# laser_driver.net
KiCad netlist of a schematic drawn in Altium Designer
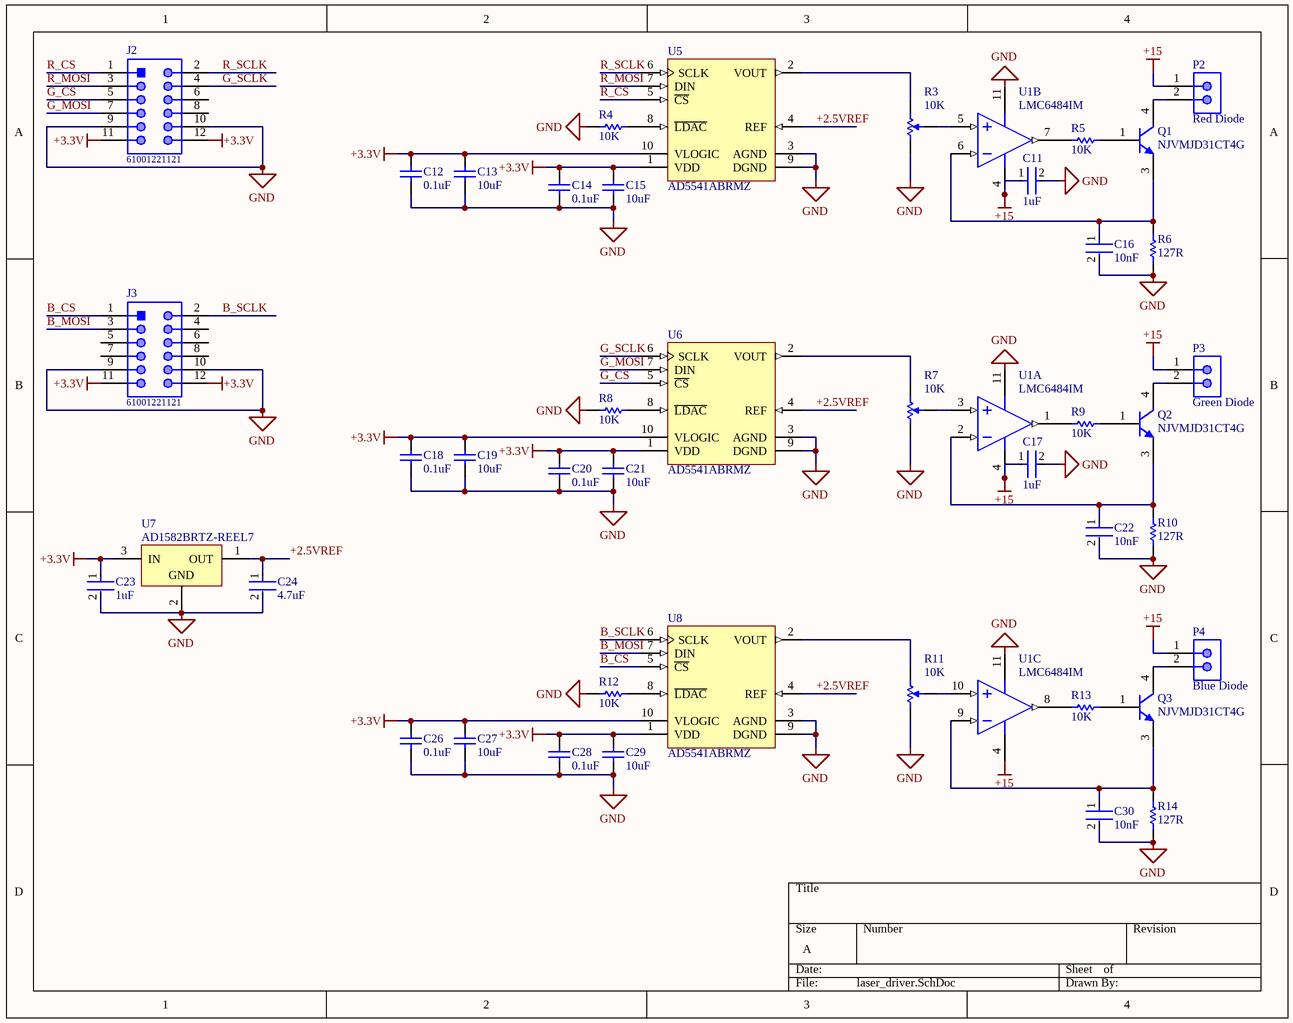
[diagram p0: laser_driver.SchDoc]

(export (version "E")
  (design (tool "Eeschema 10.0.6"))
  (components
    (comp (ref "C11")
      (value "1uF")
      (footprint "FP-CC0603-DA-MFG")
      (description "CAP CER 1UF 16V X7R 0603")
      (fields (field (name "TOLERANCE") "0.1") (field (name "MANUFACTURER") "YAGEO"))
      (libsource (lib "Altium Content Vault") (part "11868f565c42a9108669ba33697ecf6"))
    )
    (comp (ref "C12")
      (value "0.1uF")
      (footprint "CAPC1608X87X35NL15T15")
      (description "C0603X104K5RACTU")
      (fields (field (name "MANUFACTURER") "Kemet"))
      (libsource (lib "Altium Content Vault") (part "CAP"))
    )
    (comp (ref "C13")
      (value "10uF")
      (footprint "CAPC1608X90X35NL10T15")
      (description "GRM188R60J106ME47D")
      (fields (field (name "MANUFACTURER") "Murata"))
      (libsource (lib "Altium Content Vault") (part "CAP"))
    )
    (comp (ref "C14")
      (value "0.1uF")
      (footprint "CAPC1608X87X35NL15T15")
      (description "C0603X104K5RACTU")
      (fields (field (name "MANUFACTURER") "Kemet"))
      (libsource (lib "Altium Content Vault") (part "CAP"))
    )
    (comp (ref "C15")
      (value "10uF")
      (footprint "CAPC1608X90X35NL10T15")
      (description "GRM188R60J106ME47D")
      (fields (field (name "MANUFACTURER") "Murata"))
      (libsource (lib "Altium Content Vault") (part "CAP"))
    )
    (comp (ref "C16")
      (value "10nF")
      (footprint "FP-CGA3E-0_3-0_1-IPC_A")
      (description "Cap Ceramic 10nF 100V X8R 10% Pad SMD 0603 +150°C Automotive T/R")
      (fields (field (name "TOLERANCE") "10%"))
      (libsource (lib "Altium Content Vault") (part "b4654b650e69147ec39a6b967a45e02"))
    )
    (comp (ref "C17")
      (value "1uF")
      (footprint "FP-CC0603-DA-MFG")
      (description "CAP CER 1UF 16V X7R 0603")
      (fields (field (name "TOLERANCE") "0.1") (field (name "MANUFACTURER") "YAGEO"))
      (libsource (lib "Altium Content Vault") (part "11868f565c42a9108669ba33697ecf6"))
    )
    (comp (ref "C18")
      (value "0.1uF")
      (footprint "CAPC1608X87X35NL15T15")
      (description "C0603X104K5RACTU")
      (fields (field (name "MANUFACTURER") "Kemet"))
      (libsource (lib "Altium Content Vault") (part "CAP"))
    )
    (comp (ref "C19")
      (value "10uF")
      (footprint "CAPC1608X90X35NL10T15")
      (description "GRM188R60J106ME47D")
      (fields (field (name "MANUFACTURER") "Murata"))
      (libsource (lib "Altium Content Vault") (part "CAP"))
    )
    (comp (ref "C20")
      (value "0.1uF")
      (footprint "CAPC1608X87X35NL15T15")
      (description "C0603X104K5RACTU")
      (fields (field (name "MANUFACTURER") "Kemet"))
      (libsource (lib "Altium Content Vault") (part "CAP"))
    )
    (comp (ref "C21")
      (value "10uF")
      (footprint "CAPC1608X90X35NL10T15")
      (description "GRM188R60J106ME47D")
      (fields (field (name "MANUFACTURER") "Murata"))
      (libsource (lib "Altium Content Vault") (part "CAP"))
    )
    (comp (ref "C22")
      (value "10nF")
      (footprint "FP-CGA3E-0_3-0_1-IPC_A")
      (description "Cap Ceramic 10nF 100V X8R 10% Pad SMD 0603 +150°C Automotive T/R")
      (fields (field (name "TOLERANCE") "10%"))
      (libsource (lib "Altium Content Vault") (part "b4654b650e69147ec39a6b967a45e02"))
    )
    (comp (ref "C23")
      (value "1uF")
      (footprint "FP-CC0603-DA-MFG")
      (description "CAP CER 1UF 16V X7R 0603")
      (fields (field (name "TOLERANCE") "0.1") (field (name "MANUFACTURER") "YAGEO"))
      (libsource (lib "Altium Content Vault") (part "11868f565c42a9108669ba33697ecf6"))
    )
    (comp (ref "C24")
      (value "4.7uF")
      (footprint "FP-C0603-CG-MFG")
      (description "CAP CER 4.7UF 6.3V X5R 0603")
      (fields (field (name "TOLERANCE") "10%") (field (name "MANUFACTURER") "Kemet"))
      (libsource (lib "Altium Content Vault") (part "11868f565c42a9108669ba33697ecf6"))
    )
    (comp (ref "C26")
      (value "0.1uF")
      (footprint "CAPC1608X87X35NL15T15")
      (description "C0603X104K5RACTU")
      (fields (field (name "MANUFACTURER") "Kemet"))
      (libsource (lib "Altium Content Vault") (part "CAP"))
    )
    (comp (ref "C27")
      (value "10uF")
      (footprint "CAPC1608X90X35NL10T15")
      (description "GRM188R60J106ME47D")
      (fields (field (name "MANUFACTURER") "Murata"))
      (libsource (lib "Altium Content Vault") (part "CAP"))
    )
    (comp (ref "C28")
      (value "0.1uF")
      (footprint "CAPC1608X87X35NL15T15")
      (description "C0603X104K5RACTU")
      (fields (field (name "MANUFACTURER") "Kemet"))
      (libsource (lib "Altium Content Vault") (part "CAP"))
    )
    (comp (ref "C29")
      (value "10uF")
      (footprint "CAPC1608X90X35NL10T15")
      (description "GRM188R60J106ME47D")
      (fields (field (name "MANUFACTURER") "Murata"))
      (libsource (lib "Altium Content Vault") (part "CAP"))
    )
    (comp (ref "C30")
      (value "10nF")
      (footprint "FP-CGA3E-0_3-0_1-IPC_A")
      (description "Cap Ceramic 10nF 100V X8R 10% Pad SMD 0603 +150°C Automotive T/R")
      (fields (field (name "TOLERANCE") "10%"))
      (libsource (lib "Altium Content Vault") (part "b4654b650e69147ec39a6b967a45e02"))
    )
    (comp (ref "J2")
      (value "61001221121")
      (footprint "61001221121")
      (description "SMT Vertical Pin Header WR-PHD, Pitch 2.54 mm, Dual Row, 12 pins")
      (fields (field (name "MANUFACTURER") "Wurth Elektronik") (field (name "PUBLISHER") "WurthElektronik"))
      (libsource (lib "Altium Content Vault") (part "WE-CN-2P-M-R12"))
    )
    (comp (ref "J3")
      (value "61001221121")
      (footprint "61001221121")
      (description "SMT Vertical Pin Header WR-PHD, Pitch 2.54 mm, Dual Row, 12 pins")
      (fields (field (name "MANUFACTURER") "Wurth Elektronik") (field (name "PUBLISHER") "WurthElektronik"))
      (libsource (lib "Altium Content Vault") (part "WE-CN-2P-M-R12"))
    )
    (comp (ref "P2")
      (value "Red Diode")
      (footprint "JST-B2B-XH-A_V")
      (fields (field (name "MANUFACTURER") "JST"))
      (libsource (lib "Altium Content Vault") (part "CN-1P-M-R2"))
    )
    (comp (ref "P3")
      (value "Green Diode")
      (footprint "JST-B2B-XH-A_V")
      (fields (field (name "MANUFACTURER") "JST"))
      (libsource (lib "Altium Content Vault") (part "CN-1P-M-R2"))
    )
    (comp (ref "P4")
      (value "Blue Diode")
      (footprint "JST-B2B-XH-A_V")
      (fields (field (name "MANUFACTURER") "JST"))
      (libsource (lib "Altium Content Vault") (part "CN-1P-M-R2"))
    )
    (comp (ref "Q1")
      (value "NJVMJD31CT4G")
      (footprint "ONSC-DPAK-3-369C-01_V")
      (description "Complementary Power Transistor, 3-Pin DPAK, Pb-Free, Tape and Reel")
      (fields (field (name "MANUFACTURER") "On Semiconductor"))
      (libsource (lib "Altium Content Vault") (part "ONSC-NPN-B1E3C4-3"))
    )
    (comp (ref "Q2")
      (value "NJVMJD31CT4G")
      (footprint "ONSC-DPAK-3-369C-01_V")
      (description "Complementary Power Transistor, 3-Pin DPAK, Pb-Free, Tape and Reel")
      (fields (field (name "MANUFACTURER") "On Semiconductor"))
      (libsource (lib "Altium Content Vault") (part "ONSC-NPN-B1E3C4-3"))
    )
    (comp (ref "Q3")
      (value "NJVMJD31CT4G")
      (footprint "ONSC-DPAK-3-369C-01_V")
      (description "Complementary Power Transistor, 3-Pin DPAK, Pb-Free, Tape and Reel")
      (fields (field (name "MANUFACTURER") "On Semiconductor"))
      (libsource (lib "Altium Content Vault") (part "ONSC-NPN-B1E3C4-3"))
    )
    (comp (ref "R3")
      (value "10K")
      (footprint "BOUR-3313J-1_V")
      (description "Trimming Potentiometer, 10 KOhm, -55 to 125 degC, 3-Pin SMD, RoHS, Tape and Reel")
      (fields (field (name "MANUFACTURER") "Bourns"))
      (libsource (lib "Altium Content Vault") (part "RES-ADJ-3_A"))
    )
    (comp (ref "R4")
      (value "10K")
      (footprint "RESC1609X55X30LL15T15")
      (description "Chip Resistor, 10 KOhm, +/- 1%, 0.1 W, -55 to 155 degC, 0603 (1608 Metric), RoHS, Tape and Reel")
      (fields (field (name "TOLERANCE") "1%") (field (name "MANUFACTURER") "Panasonic"))
      (libsource (lib "Altium Content Vault") (part "RES-2"))
    )
    (comp (ref "R5")
      (value "10K")
      (footprint "RESC1609X55X30LL15T15")
      (description "Chip Resistor, 10 KOhm, +/- 1%, 0.1 W, -55 to 155 degC, 0603 (1608 Metric), RoHS, Tape and Reel")
      (fields (field (name "TOLERANCE") "1%") (field (name "MANUFACTURER") "Panasonic"))
      (libsource (lib "Altium Content Vault") (part "RES-2"))
    )
    (comp (ref "R6")
      (value "127R")
      (footprint "RESC1608X55X30LL15T15")
      (description "ERJ-3EKF1270V")
      (fields (field (name "MANUFACTURER") "Panasonic"))
      (libsource (lib "Altium Content Vault") (part "RES"))
    )
    (comp (ref "R7")
      (value "10K")
      (footprint "BOUR-3313J-1_V")
      (description "Trimming Potentiometer, 10 KOhm, -55 to 125 degC, 3-Pin SMD, RoHS, Tape and Reel")
      (fields (field (name "MANUFACTURER") "Bourns"))
      (libsource (lib "Altium Content Vault") (part "RES-ADJ-3_A"))
    )
    (comp (ref "R8")
      (value "10K")
      (footprint "RESC1609X55X30LL15T15")
      (description "Chip Resistor, 10 KOhm, +/- 1%, 0.1 W, -55 to 155 degC, 0603 (1608 Metric), RoHS, Tape and Reel")
      (fields (field (name "TOLERANCE") "1%") (field (name "MANUFACTURER") "Panasonic"))
      (libsource (lib "Altium Content Vault") (part "RES-2"))
    )
    (comp (ref "R9")
      (value "10K")
      (footprint "RESC1609X55X30LL15T15")
      (description "Chip Resistor, 10 KOhm, +/- 1%, 0.1 W, -55 to 155 degC, 0603 (1608 Metric), RoHS, Tape and Reel")
      (fields (field (name "TOLERANCE") "1%") (field (name "MANUFACTURER") "Panasonic"))
      (libsource (lib "Altium Content Vault") (part "RES-2"))
    )
    (comp (ref "R10")
      (value "127R")
      (footprint "RESC1608X55X30LL15T15")
      (description "ERJ-3EKF1270V")
      (fields (field (name "MANUFACTURER") "Panasonic"))
      (libsource (lib "Altium Content Vault") (part "RES"))
    )
    (comp (ref "R11")
      (value "10K")
      (footprint "BOUR-3313J-1_V")
      (description "Trimming Potentiometer, 10 KOhm, -55 to 125 degC, 3-Pin SMD, RoHS, Tape and Reel")
      (fields (field (name "MANUFACTURER") "Bourns"))
      (libsource (lib "Altium Content Vault") (part "RES-ADJ-3_A"))
    )
    (comp (ref "R12")
      (value "10K")
      (footprint "RESC1609X55X30LL15T15")
      (description "Chip Resistor, 10 KOhm, +/- 1%, 0.1 W, -55 to 155 degC, 0603 (1608 Metric), RoHS, Tape and Reel")
      (fields (field (name "TOLERANCE") "1%") (field (name "MANUFACTURER") "Panasonic"))
      (libsource (lib "Altium Content Vault") (part "RES-2"))
    )
    (comp (ref "R13")
      (value "10K")
      (footprint "RESC1609X55X30LL15T15")
      (description "Chip Resistor, 10 KOhm, +/- 1%, 0.1 W, -55 to 155 degC, 0603 (1608 Metric), RoHS, Tape and Reel")
      (fields (field (name "TOLERANCE") "1%") (field (name "MANUFACTURER") "Panasonic"))
      (libsource (lib "Altium Content Vault") (part "RES-2"))
    )
    (comp (ref "R14")
      (value "127R")
      (footprint "RESC1608X55X30LL15T15")
      (description "ERJ-3EKF1270V")
      (fields (field (name "MANUFACTURER") "Panasonic"))
      (libsource (lib "Altium Content Vault") (part "RES"))
    )
    (comp (ref "U1")
      (value "LMC6484IM")
      (footprint "D0014A_N")
      (description "CMOS Quad Rail to Rail Input and Output Operational Amplifier, 14-pin Narrow SOIC, Pb-Free")
      (fields (field (name "MANUFACTURER") "Texas Instruments"))
      (libsource (lib "Altium Content Vault") (part "AMP-OPA-LF147-14"))
    )
    (comp (ref "U5")
      (value "AD5541ABRMZ")
      (footprint "RM-10_L")
      (fields (field (name "GENERIC PART NUMBER") "AD5541A") (field (name "MANUFACTURER") "Analog Devices"))
      (libsource (lib "Altium Content Vault") (part "ADI-AD5541A-RM-10"))
    )
    (comp (ref "U6")
      (value "AD5541ABRMZ")
      (footprint "RM-10_L")
      (fields (field (name "GENERIC PART NUMBER") "AD5541A") (field (name "MANUFACTURER") "Analog Devices"))
      (libsource (lib "Altium Content Vault") (part "ADI-AD5541A-RM-10"))
    )
    (comp (ref "U7")
      (value "AD1582BRTZ-REEL7")
      (footprint "ADI-RT-3_M")
      (fields (field (name "MANUFACTURER") "Analog Devices"))
      (libsource (lib "Altium Content Vault") (part "ADI-AD158X-RT-3"))
    )
    (comp (ref "U8")
      (value "AD5541ABRMZ")
      (footprint "RM-10_L")
      (fields (field (name "GENERIC PART NUMBER") "AD5541A") (field (name "MANUFACTURER") "Analog Devices"))
      (libsource (lib "Altium Content Vault") (part "ADI-AD5541A-RM-10"))
    )
  )
  (nets
    (net (code "1") (name "+3.3V") (class "Default")
      (node (ref "C12") (pin "1") (pinfunction "1_1") (pintype "passive"))
      (node (ref "C13") (pin "2") (pinfunction "2_2") (pintype "passive"))
      (node (ref "C14") (pin "1") (pinfunction "1_1") (pintype "passive"))
      (node (ref "C15") (pin "2") (pinfunction "2_2") (pintype "passive"))
      (node (ref "C18") (pin "1") (pinfunction "1_1") (pintype "passive"))
      (node (ref "C19") (pin "2") (pinfunction "2_2") (pintype "passive"))
      (node (ref "C20") (pin "1") (pinfunction "1_1") (pintype "passive"))
      (node (ref "C21") (pin "2") (pinfunction "2_2") (pintype "passive"))
      (node (ref "C23") (pin "1") (pinfunction "1_1") (pintype "passive"))
      (node (ref "C26") (pin "1") (pinfunction "1_1") (pintype "passive"))
      (node (ref "C27") (pin "2") (pinfunction "2_2") (pintype "passive"))
      (node (ref "C28") (pin "1") (pinfunction "1_1") (pintype "passive"))
      (node (ref "C29") (pin "2") (pinfunction "2_2") (pintype "passive"))
      (node (ref "J2") (pin "11") (pinfunction "11_11") (pintype "passive"))
      (node (ref "J2") (pin "12") (pinfunction "12_12") (pintype "passive"))
      (node (ref "J3") (pin "11") (pinfunction "11_11") (pintype "passive"))
      (node (ref "J3") (pin "12") (pinfunction "12_12") (pintype "passive"))
      (node (ref "U5") (pin "1") (pinfunction "VDD_1") (pintype "power_in"))
      (node (ref "U5") (pin "10") (pinfunction "VLOGIC_10") (pintype "power_in"))
      (node (ref "U6") (pin "1") (pinfunction "VDD_1") (pintype "power_in"))
      (node (ref "U6") (pin "10") (pinfunction "VLOGIC_10") (pintype "power_in"))
      (node (ref "U7") (pin "3") (pinfunction "IN_3") (pintype "power_in"))
      (node (ref "U8") (pin "1") (pinfunction "VDD_1") (pintype "power_in"))
      (node (ref "U8") (pin "10") (pinfunction "VLOGIC_10") (pintype "power_in"))
    )
    (net (code "2") (name "+15") (class "Default")
      (node (ref "C11") (pin "1") (pinfunction "1_1") (pintype "passive"))
      (node (ref "C17") (pin "1") (pinfunction "1_1") (pintype "passive"))
      (node (ref "P2") (pin "1") (pinfunction "1_1") (pintype "passive"))
      (node (ref "P3") (pin "1") (pinfunction "1_1") (pintype "passive"))
      (node (ref "P4") (pin "1") (pinfunction "1_1") (pintype "passive"))
      (node (ref "U1") (pin "4") (pinfunction "V+_4") (pintype "power_in"))
    )
    (net (code "3") (name "/+2.5VREF") (class "Default")
      (node (ref "C24") (pin "1") (pinfunction "1_1") (pintype "passive"))
      (node (ref "U5") (pin "4") (pinfunction "REF_4") (pintype "input"))
      (node (ref "U6") (pin "4") (pinfunction "REF_4") (pintype "input"))
      (node (ref "U7") (pin "1") (pinfunction "OUT_1") (pintype "power_in"))
      (node (ref "U8") (pin "4") (pinfunction "REF_4") (pintype "input"))
    )
    (net (code "4") (name "/B_CS") (class "Default")
      (node (ref "J3") (pin "1") (pinfunction "1_1") (pintype "passive"))
      (node (ref "U8") (pin "5") (pinfunction "~{CS}_5") (pintype "input"))
    )
    (net (code "5") (name "/B_MOSI") (class "Default")
      (node (ref "J3") (pin "3") (pinfunction "3_3") (pintype "passive"))
      (node (ref "U8") (pin "7") (pinfunction "DIN_7") (pintype "input"))
    )
    (net (code "6") (name "/B_SCLK") (class "Default")
      (node (ref "J3") (pin "2") (pinfunction "2_2") (pintype "passive"))
      (node (ref "U8") (pin "6") (pinfunction "SCLK_6") (pintype "input"))
    )
    (net (code "7") (name "/G_CS") (class "Default")
      (node (ref "J2") (pin "5") (pinfunction "5_5") (pintype "passive"))
      (node (ref "U6") (pin "5") (pinfunction "~{CS}_5") (pintype "input"))
    )
    (net (code "8") (name "/G_MOSI") (class "Default")
      (node (ref "J2") (pin "7") (pinfunction "7_7") (pintype "passive"))
      (node (ref "U6") (pin "7") (pinfunction "DIN_7") (pintype "input"))
    )
    (net (code "9") (name "/G_SCLK") (class "Default")
      (node (ref "J2") (pin "4") (pinfunction "4_4") (pintype "passive"))
      (node (ref "U6") (pin "6") (pinfunction "SCLK_6") (pintype "input"))
    )
    (net (code "10") (name "/R_CS") (class "Default")
      (node (ref "J2") (pin "1") (pinfunction "1_1") (pintype "passive"))
      (node (ref "U5") (pin "5") (pinfunction "~{CS}_5") (pintype "input"))
    )
    (net (code "11") (name "/R_MOSI") (class "Default")
      (node (ref "J2") (pin "3") (pinfunction "3_3") (pintype "passive"))
      (node (ref "U5") (pin "7") (pinfunction "DIN_7") (pintype "input"))
    )
    (net (code "12") (name "/R_SCLK") (class "Default")
      (node (ref "J2") (pin "2") (pinfunction "2_2") (pintype "passive"))
      (node (ref "U5") (pin "6") (pinfunction "SCLK_6") (pintype "input"))
    )
    (net (code "13") (name "GND") (class "Default")
      (node (ref "C11") (pin "2") (pinfunction "2_2") (pintype "passive"))
      (node (ref "C12") (pin "2") (pinfunction "2_2") (pintype "passive"))
      (node (ref "C13") (pin "1") (pinfunction "1_1") (pintype "passive"))
      (node (ref "C14") (pin "2") (pinfunction "2_2") (pintype "passive"))
      (node (ref "C15") (pin "1") (pinfunction "1_1") (pintype "passive"))
      (node (ref "C16") (pin "2") (pinfunction "2_2") (pintype "passive"))
      (node (ref "C17") (pin "2") (pinfunction "2_2") (pintype "passive"))
      (node (ref "C18") (pin "2") (pinfunction "2_2") (pintype "passive"))
      (node (ref "C19") (pin "1") (pinfunction "1_1") (pintype "passive"))
      (node (ref "C20") (pin "2") (pinfunction "2_2") (pintype "passive"))
      (node (ref "C21") (pin "1") (pinfunction "1_1") (pintype "passive"))
      (node (ref "C22") (pin "2") (pinfunction "2_2") (pintype "passive"))
      (node (ref "C23") (pin "2") (pinfunction "2_2") (pintype "passive"))
      (node (ref "C24") (pin "2") (pinfunction "2_2") (pintype "passive"))
      (node (ref "C26") (pin "2") (pinfunction "2_2") (pintype "passive"))
      (node (ref "C27") (pin "1") (pinfunction "1_1") (pintype "passive"))
      (node (ref "C28") (pin "2") (pinfunction "2_2") (pintype "passive"))
      (node (ref "C29") (pin "1") (pinfunction "1_1") (pintype "passive"))
      (node (ref "C30") (pin "2") (pinfunction "2_2") (pintype "passive"))
      (node (ref "J2") (pin "10") (pinfunction "10_10") (pintype "passive"))
      (node (ref "J2") (pin "9") (pinfunction "9_9") (pintype "passive"))
      (node (ref "J3") (pin "10") (pinfunction "10_10") (pintype "passive"))
      (node (ref "J3") (pin "9") (pinfunction "9_9") (pintype "passive"))
      (node (ref "R10") (pin "1") (pinfunction "1_1") (pintype "passive"))
      (node (ref "R11") (pin "1") (pinfunction "1_1") (pintype "passive"))
      (node (ref "R12") (pin "2") (pinfunction "2_2") (pintype "passive"))
      (node (ref "R14") (pin "1") (pinfunction "1_1") (pintype "passive"))
      (node (ref "R3") (pin "1") (pinfunction "1_1") (pintype "passive"))
      (node (ref "R4") (pin "2") (pinfunction "2_2") (pintype "passive"))
      (node (ref "R6") (pin "1") (pinfunction "1_1") (pintype "passive"))
      (node (ref "R7") (pin "1") (pinfunction "1_1") (pintype "passive"))
      (node (ref "R8") (pin "2") (pinfunction "2_2") (pintype "passive"))
      (node (ref "U1") (pin "11") (pinfunction "V-_11") (pintype "power_in"))
      (node (ref "U5") (pin "3") (pinfunction "AGND_3") (pintype "power_in"))
      (node (ref "U5") (pin "9") (pinfunction "DGND_9") (pintype "power_in"))
      (node (ref "U6") (pin "3") (pinfunction "AGND_3") (pintype "power_in"))
      (node (ref "U6") (pin "9") (pinfunction "DGND_9") (pintype "power_in"))
      (node (ref "U7") (pin "2") (pinfunction "GND_2") (pintype "power_in"))
      (node (ref "U8") (pin "3") (pinfunction "AGND_3") (pintype "power_in"))
      (node (ref "U8") (pin "9") (pinfunction "DGND_9") (pintype "power_in"))
    )
    (net (code "14") (name "Net-(Q1-B)") (class "Default")
      (node (ref "Q1") (pin "1") (pinfunction "B_1") (pintype "passive"))
      (node (ref "R5") (pin "2") (pinfunction "2_2") (pintype "passive"))
    )
    (net (code "15") (name "Net-(Q1-C)") (class "Default")
      (node (ref "P2") (pin "2") (pinfunction "2_2") (pintype "passive"))
      (node (ref "Q1") (pin "4") (pinfunction "C_4") (pintype "passive"))
    )
    (net (code "16") (name "Net-(Q1-E)") (class "Default")
      (node (ref "C16") (pin "1") (pinfunction "1_1") (pintype "passive"))
      (node (ref "Q1") (pin "3") (pinfunction "E_3") (pintype "passive"))
      (node (ref "R6") (pin "2") (pinfunction "2_2") (pintype "passive"))
      (node (ref "U1") (pin "6") (pinfunction "IN2-_6") (pintype "input"))
    )
    (net (code "17") (name "Net-(Q2-B)") (class "Default")
      (node (ref "Q2") (pin "1") (pinfunction "B_1") (pintype "passive"))
      (node (ref "R9") (pin "2") (pinfunction "2_2") (pintype "passive"))
    )
    (net (code "18") (name "Net-(Q2-C)") (class "Default")
      (node (ref "P3") (pin "2") (pinfunction "2_2") (pintype "passive"))
      (node (ref "Q2") (pin "4") (pinfunction "C_4") (pintype "passive"))
    )
    (net (code "19") (name "Net-(Q2-E)") (class "Default")
      (node (ref "C22") (pin "1") (pinfunction "1_1") (pintype "passive"))
      (node (ref "Q2") (pin "3") (pinfunction "E_3") (pintype "passive"))
      (node (ref "R10") (pin "2") (pinfunction "2_2") (pintype "passive"))
      (node (ref "U1") (pin "2") (pinfunction "IN1-_2") (pintype "input"))
    )
    (net (code "20") (name "Net-(Q3-B)") (class "Default")
      (node (ref "Q3") (pin "1") (pinfunction "B_1") (pintype "passive"))
      (node (ref "R13") (pin "2") (pinfunction "2_2") (pintype "passive"))
    )
    (net (code "21") (name "Net-(Q3-C)") (class "Default")
      (node (ref "P4") (pin "2") (pinfunction "2_2") (pintype "passive"))
      (node (ref "Q3") (pin "4") (pinfunction "C_4") (pintype "passive"))
    )
    (net (code "22") (name "Net-(Q3-E)") (class "Default")
      (node (ref "C30") (pin "1") (pinfunction "1_1") (pintype "passive"))
      (node (ref "Q3") (pin "3") (pinfunction "E_3") (pintype "passive"))
      (node (ref "R14") (pin "2") (pinfunction "2_2") (pintype "passive"))
      (node (ref "U1") (pin "9") (pinfunction "IN3-_9") (pintype "input"))
    )
    (net (code "23") (name "Net-(U1A-IN1+)") (class "Default")
      (node (ref "R7") (pin "2") (pinfunction "2_2") (pintype "passive"))
      (node (ref "U1") (pin "3") (pinfunction "IN1+_3") (pintype "input"))
    )
    (net (code "24") (name "Net-(U1A-OUT1)") (class "Default")
      (node (ref "R9") (pin "1") (pinfunction "1_1") (pintype "passive"))
      (node (ref "U1") (pin "1") (pinfunction "OUT1_1") (pintype "output"))
    )
    (net (code "25") (name "Net-(U1B-IN2+)") (class "Default")
      (node (ref "R3") (pin "2") (pinfunction "2_2") (pintype "passive"))
      (node (ref "U1") (pin "5") (pinfunction "IN2+_5") (pintype "input"))
    )
    (net (code "26") (name "Net-(U1B-OUT2)") (class "Default")
      (node (ref "R5") (pin "1") (pinfunction "1_1") (pintype "passive"))
      (node (ref "U1") (pin "7") (pinfunction "OUT2_7") (pintype "output"))
    )
    (net (code "27") (name "Net-(U1C-IN3+)") (class "Default")
      (node (ref "R11") (pin "2") (pinfunction "2_2") (pintype "passive"))
      (node (ref "U1") (pin "10") (pinfunction "IN3+_10") (pintype "input"))
    )
    (net (code "28") (name "Net-(U1C-OUT3)") (class "Default")
      (node (ref "R13") (pin "1") (pinfunction "1_1") (pintype "passive"))
      (node (ref "U1") (pin "8") (pinfunction "OUT3_8") (pintype "output"))
    )
    (net (code "29") (name "Net-(U5-VOUT)") (class "Default")
      (node (ref "R3") (pin "3") (pinfunction "3_3") (pintype "passive"))
      (node (ref "U5") (pin "2") (pinfunction "VOUT_2") (pintype "output"))
    )
    (net (code "30") (name "Net-(U5-~{LDAC})") (class "Default")
      (node (ref "R4") (pin "1") (pinfunction "1_1") (pintype "passive"))
      (node (ref "U5") (pin "8") (pinfunction "~{LDAC}_8") (pintype "input"))
    )
    (net (code "31") (name "Net-(U6-VOUT)") (class "Default")
      (node (ref "R7") (pin "3") (pinfunction "3_3") (pintype "passive"))
      (node (ref "U6") (pin "2") (pinfunction "VOUT_2") (pintype "output"))
    )
    (net (code "32") (name "Net-(U6-~{LDAC})") (class "Default")
      (node (ref "R8") (pin "1") (pinfunction "1_1") (pintype "passive"))
      (node (ref "U6") (pin "8") (pinfunction "~{LDAC}_8") (pintype "input"))
    )
    (net (code "33") (name "Net-(U8-VOUT)") (class "Default")
      (node (ref "R11") (pin "3") (pinfunction "3_3") (pintype "passive"))
      (node (ref "U8") (pin "2") (pinfunction "VOUT_2") (pintype "output"))
    )
    (net (code "34") (name "Net-(U8-~{LDAC})") (class "Default")
      (node (ref "R12") (pin "1") (pinfunction "1_1") (pintype "passive"))
      (node (ref "U8") (pin "8") (pinfunction "~{LDAC}_8") (pintype "input"))
    )
    (net (code "35") (name "unconnected-(J2-Pad6)") (class "Default")
      (node (ref "J2") (pin "6") (pinfunction "6_6") (pintype "passive"))
    )
    (net (code "36") (name "unconnected-(J2-Pad8)") (class "Default")
      (node (ref "J2") (pin "8") (pinfunction "8_8") (pintype "passive"))
    )
    (net (code "37") (name "unconnected-(J3-Pad4)") (class "Default")
      (node (ref "J3") (pin "4") (pinfunction "4_4") (pintype "passive"))
    )
    (net (code "38") (name "unconnected-(J3-Pad5)") (class "Default")
      (node (ref "J3") (pin "5") (pinfunction "5_5") (pintype "passive"))
    )
    (net (code "39") (name "unconnected-(J3-Pad6)") (class "Default")
      (node (ref "J3") (pin "6") (pinfunction "6_6") (pintype "passive"))
    )
    (net (code "40") (name "unconnected-(J3-Pad7)") (class "Default")
      (node (ref "J3") (pin "7") (pinfunction "7_7") (pintype "passive"))
    )
    (net (code "41") (name "unconnected-(J3-Pad8)") (class "Default")
      (node (ref "J3") (pin "8") (pinfunction "8_8") (pintype "passive"))
    )
  )
)
